# schematic.net
KiCad netlist of a schematic drawn in EasyEDA
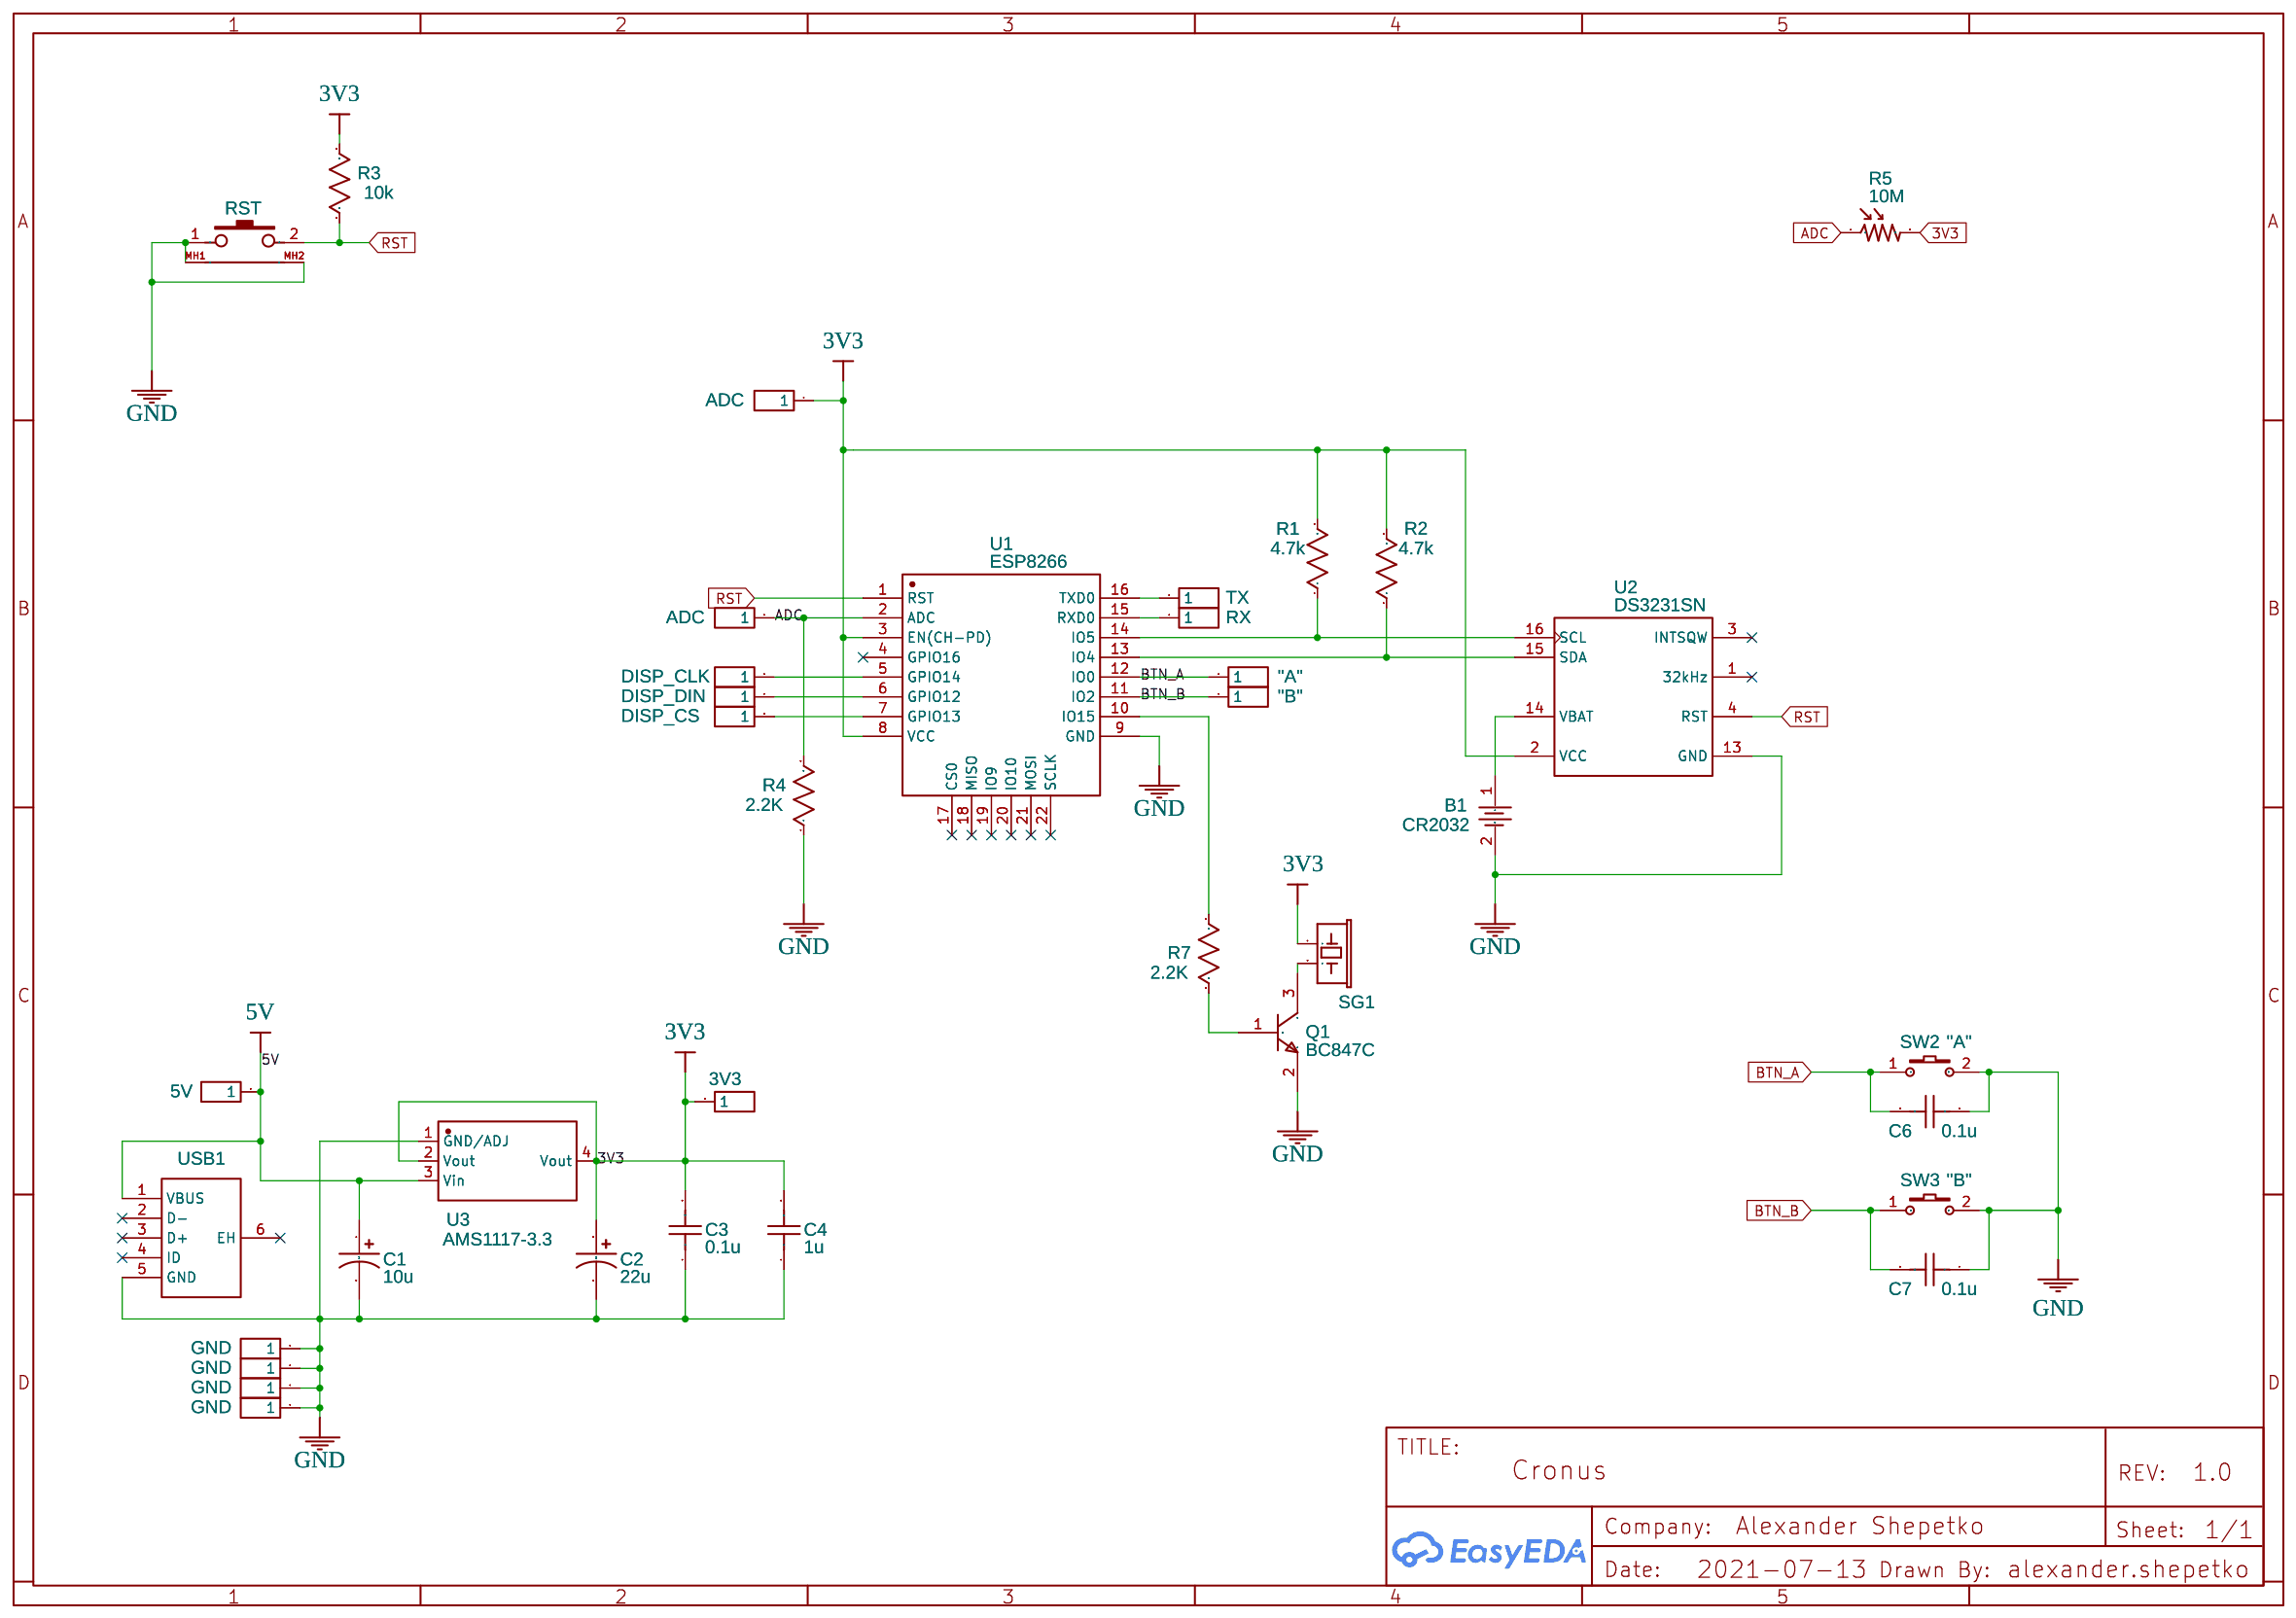
[diagram p0: schematic sheet]

(export (version "E")
  (design (tool "Eeschema 10.0.6"))
  (components
    (comp (ref "B1")
      (value "CR2032")
      (fields (field (name "BOM_Manufacturer Part") "BS-2-1") (field (name "BOM_Supplier Part") "C70376"))
      (libsource (lib "") (part "CR2032-BS-2-1"))
    )
    (comp (ref "C1") (value "10u") (libsource (lib "") (part "C_Tan_SMD_A_US")))
    (comp (ref "C2") (value "22u") (libsource (lib "") (part "C_Tan_SMD_A_US_1")))
    (comp (ref "C3") (value "0.1u") (libsource (lib "") (part "C_0603_US")))
    (comp (ref "C4") (value "1u") (libsource (lib "") (part "C_0603_US")))
    (comp (ref "C6") (value "0.1u") (libsource (lib "") (part "C_0603_US_1")))
    (comp (ref "C7") (value "0.1u") (libsource (lib "") (part "C_0603_US_1")))
    (comp (ref "J1")
      (value "DISP_CLK")
      (fields (field (name "BOM_Supplier Part") "C81276"))
      (libsource (lib "") (part "HDR-M-2.54_1x1_1"))
    )
    (comp (ref "J2")
      (value "DISP_DIN")
      (fields (field (name "BOM_Supplier Part") "C81276"))
      (libsource (lib "") (part "HDR-M-2.54_1x1_1"))
    )
    (comp (ref "J3")
      (value "DISP_CS")
      (fields (field (name "BOM_Supplier Part") "C81276"))
      (libsource (lib "") (part "HDR-M-2.54_1x1_1"))
    )
    (comp (ref "J4")
      (value "\"A\"")
      (fields (field (name "BOM_Supplier Part") "C81276"))
      (libsource (lib "") (part "HDR-M-2.54_1x1"))
    )
    (comp (ref "J5")
      (value "TX")
      (fields (field (name "BOM_Supplier Part") "C81276"))
      (libsource (lib "") (part "HDR-M-2.54_1x1"))
    )
    (comp (ref "J6")
      (value "RX")
      (fields (field (name "BOM_Supplier Part") "C81276"))
      (libsource (lib "") (part "HDR-M-2.54_1x1"))
    )
    (comp (ref "J7")
      (value "\"B\"")
      (fields (field (name "BOM_Supplier Part") "C81276"))
      (libsource (lib "") (part "HDR-M-2.54_1x1"))
    )
    (comp (ref "J8")
      (value "ADC")
      (fields (field (name "BOM_Supplier Part") "C81276"))
      (libsource (lib "") (part "HDR-M-2.54_1x1_1"))
    )
    (comp (ref "J9")
      (value "GND")
      (fields (field (name "BOM_Supplier Part") "C81276"))
      (libsource (lib "") (part "HDR-M-2.54_1x1_1"))
    )
    (comp (ref "J10")
      (value "ADC")
      (fields (field (name "BOM_Supplier Part") "C81276"))
      (libsource (lib "") (part "HDR-M-2.54_1x1_1"))
    )
    (comp (ref "J11")
      (value "GND")
      (fields (field (name "BOM_Supplier Part") "C81276"))
      (libsource (lib "") (part "HDR-M-2.54_1x1_1"))
    )
    (comp (ref "J12")
      (value "5V")
      (fields (field (name "BOM_Supplier Part") "C81276"))
      (libsource (lib "") (part "HDR-M-2.54_1x1_1"))
    )
    (comp (ref "J13")
      (value "GND")
      (fields (field (name "BOM_Supplier Part") "C81276"))
      (libsource (lib "") (part "HDR-M-2.54_1x1_1"))
    )
    (comp (ref "J14")
      (value "GND")
      (fields (field (name "BOM_Supplier Part") "C81276"))
      (libsource (lib "") (part "HDR-M-2.54_1x1_1"))
    )
    (comp (ref "J15")
      (value "3V3")
      (fields (field (name "BOM_Supplier Part") "C81276"))
      (libsource (lib "") (part "HDR-M-2.54_1x1"))
    )
    (comp (ref "Q1") (value "BC847C") (libsource (lib "") (part "BC847CLT3")))
    (comp (ref "R1") (value "4.7k") (libsource (lib "") (part "R_0603_US")))
    (comp (ref "R2") (value "4.7k") (libsource (lib "") (part "R_0603_US")))
    (comp (ref "R3") (value "10k") (libsource (lib "") (part "R_0603_US")))
    (comp (ref "R4") (value "2.2K") (libsource (lib "") (part "R_0603_US")))
    (comp (ref "R5") (value "10M") (libsource (lib "") (part "PHOTORESPDV-P9")))
    (comp (ref "R7") (value "2.2K") (libsource (lib "") (part "R_0603_US_1")))
    (comp (ref "SG1") (value "BUZZER") (libsource (lib "") (part "BUZZER")))
    (comp (ref "SW1")
      (value "RST")
      (fields
        (field (name "BOM_Manufacturer Part") "Switch,6*6*9Plastic head,260G, 0.25mm,Side bracket")
        (field (name "BOM_Supplier Part") "C71842")
      )
      (libsource (lib "") (part "Button-6x6x9-Right-Angle"))
    )
    (comp (ref "SW2")
      (value "\"A\"")
      (fields
        (field (name "BOM_Manufacturer Part") "K2-1107ST-A4SW-06")
        (field (name "BOM_Supplier Part") "C118141")
      )
      (libsource (lib "") (part "K2-3.6×6.1_SMD"))
    )
    (comp (ref "SW3")
      (value "\"B\"")
      (fields
        (field (name "BOM_Manufacturer Part") "K2-1107ST-A4SW-06")
        (field (name "BOM_Supplier Part") "C118141")
      )
      (libsource (lib "") (part "K2-3.6×6.1_SMD"))
    )
    (comp (ref "U1")
      (value "ESP8266")
      (fields
        (field (name "BOM_Manufacturer Part") "ESP-12F(ESP8266MOD)")
        (field (name "BOM_Supplier Part") "C82891")
      )
      (libsource (lib "") (part "ESP-12F(ESP8266MOD)"))
    )
    (comp (ref "U2")
      (value "DS3231SN")
      (fields (field (name "BOM_Supplier Part") "C9866"))
      (libsource (lib "") (part "DS3231SN#"))
    )
    (comp (ref "U3")
      (value "AMS1117-3.3")
      (fields (field (name "BOM_Supplier Part") "C6186"))
      (libsource (lib "") (part "AMS1117-3.3"))
    )
    (comp (ref "USB1")
      (value "A4A0505-C-30-R")
      (fields (field (name "BOM_Supplier Part") "C694908"))
      (libsource (lib "") (part "A4A0505-C-30-R"))
    )
  )
  (nets
    (net (code "1") (name "3V3") (class "Default")
      (node (ref "C2") (pin "2") (pinfunction "1_2") (pintype "unspecified"))
      (node (ref "C3") (pin "2") (pinfunction "2_2") (pintype "unspecified"))
      (node (ref "C4") (pin "2") (pinfunction "2_2") (pintype "unspecified"))
      (node (ref "J10") (pin "1") (pinfunction "1_1") (pintype "input"))
      (node (ref "J15") (pin "1") (pinfunction "1_1") (pintype "input"))
      (node (ref "R1") (pin "2") (pinfunction "2_2") (pintype "unspecified"))
      (node (ref "R2") (pin "2") (pinfunction "2_2") (pintype "unspecified"))
      (node (ref "R3") (pin "2") (pinfunction "2_2") (pintype "unspecified"))
      (node (ref "R5") (pin "2") (pinfunction "2_2") (pintype "unspecified"))
      (node (ref "SG1") (pin "1") (pinfunction "1_1") (pintype "unspecified"))
      (node (ref "U1") (pin "3") (pinfunction "EN(CH-PD)_3") (pintype "unspecified"))
      (node (ref "U1") (pin "8") (pinfunction "VCC_8") (pintype "unspecified"))
      (node (ref "U2") (pin "2") (pinfunction "VCC_2") (pintype "passive"))
      (node (ref "U3") (pin "2") (pinfunction "Vout_2") (pintype "unspecified"))
      (node (ref "U3") (pin "4") (pinfunction "Vout_4") (pintype "unspecified"))
    )
    (net (code "2") (name "5V") (class "Default")
      (node (ref "C1") (pin "1") (pinfunction "1_1") (pintype "unspecified"))
      (node (ref "J12") (pin "1") (pinfunction "1_1") (pintype "input"))
      (node (ref "U3") (pin "3") (pinfunction "Vin_3") (pintype "unspecified"))
      (node (ref "USB1") (pin "1") (pinfunction "VBUS_1") (pintype "unspecified"))
    )
    (net (code "3") (name "ADC") (class "Default")
      (node (ref "J8") (pin "1") (pinfunction "1_1") (pintype "input"))
      (node (ref "R4") (pin "2") (pinfunction "2_2") (pintype "unspecified"))
      (node (ref "R5") (pin "1") (pinfunction "1_1") (pintype "unspecified"))
      (node (ref "U1") (pin "2") (pinfunction "ADC_2") (pintype "unspecified"))
    )
    (net (code "4") (name "BTN_A") (class "Default")
      (node (ref "C6") (pin "2") (pinfunction "2_2") (pintype "unspecified"))
      (node (ref "J4") (pin "1") (pinfunction "1_1") (pintype "input"))
      (node (ref "SW2") (pin "1") (pinfunction "1_1") (pintype "unspecified"))
      (node (ref "U1") (pin "12") (pinfunction "IO0_12") (pintype "unspecified"))
    )
    (net (code "5") (name "BTN_B") (class "Default")
      (node (ref "C7") (pin "2") (pinfunction "2_2") (pintype "unspecified"))
      (node (ref "J7") (pin "1") (pinfunction "1_1") (pintype "input"))
      (node (ref "SW3") (pin "1") (pinfunction "1_1") (pintype "unspecified"))
      (node (ref "U1") (pin "11") (pinfunction "IO2_11") (pintype "unspecified"))
    )
    (net (code "6") (name "GND") (class "Default")
      (node (ref "B1") (pin "2") (pinfunction "2_2") (pintype "input"))
      (node (ref "C1") (pin "2") (pinfunction "2_2") (pintype "unspecified"))
      (node (ref "C2") (pin "1") (pinfunction "2_1") (pintype "unspecified"))
      (node (ref "C3") (pin "1") (pinfunction "1_1") (pintype "unspecified"))
      (node (ref "C4") (pin "1") (pinfunction "1_1") (pintype "unspecified"))
      (node (ref "C6") (pin "1") (pinfunction "1_1") (pintype "unspecified"))
      (node (ref "C7") (pin "1") (pinfunction "1_1") (pintype "unspecified"))
      (node (ref "J11") (pin "1") (pinfunction "1_1") (pintype "input"))
      (node (ref "J13") (pin "1") (pinfunction "1_1") (pintype "input"))
      (node (ref "J14") (pin "1") (pinfunction "1_1") (pintype "input"))
      (node (ref "J9") (pin "1") (pinfunction "1_1") (pintype "input"))
      (node (ref "Q1") (pin "2") (pinfunction "E_2") (pintype "unspecified"))
      (node (ref "R4") (pin "1") (pinfunction "1_1") (pintype "unspecified"))
      (node (ref "SW1") (pin "1") (pinfunction "1_1") (pintype "input"))
      (node (ref "SW1") (pin "MH1") (pinfunction "MH1_MH1") (pintype "input"))
      (node (ref "SW1") (pin "MH2") (pinfunction "MH2_MH2") (pintype "input"))
      (node (ref "SW2") (pin "2") (pinfunction "2_2") (pintype "unspecified"))
      (node (ref "SW3") (pin "2") (pinfunction "2_2") (pintype "unspecified"))
      (node (ref "U1") (pin "9") (pinfunction "GND_9") (pintype "unspecified"))
      (node (ref "U2") (pin "13") (pinfunction "GND_13") (pintype "passive"))
      (node (ref "U3") (pin "1") (pinfunction "GND/ADJ_1") (pintype "unspecified"))
      (node (ref "USB1") (pin "5") (pinfunction "GND_5") (pintype "unspecified"))
    )
    (net (code "7") (name "Net-(Q1-B)") (class "Default")
      (node (ref "Q1") (pin "1") (pinfunction "B_1") (pintype "unspecified"))
      (node (ref "R7") (pin "2") (pinfunction "2_2") (pintype "unspecified"))
    )
    (net (code "8") (name "Net-(Q1-C)") (class "Default")
      (node (ref "Q1") (pin "3") (pinfunction "C_3") (pintype "unspecified"))
      (node (ref "SG1") (pin "2") (pinfunction "1_2") (pintype "unspecified"))
    )
    (net (code "9") (name "Net-(U1-GPIO12)") (class "Default")
      (node (ref "J2") (pin "1") (pinfunction "1_1") (pintype "input"))
      (node (ref "U1") (pin "6") (pinfunction "GPIO12_6") (pintype "unspecified"))
    )
    (net (code "10") (name "Net-(U1-GPIO13)") (class "Default")
      (node (ref "J3") (pin "1") (pinfunction "1_1") (pintype "input"))
      (node (ref "U1") (pin "7") (pinfunction "GPIO13_7") (pintype "unspecified"))
    )
    (net (code "11") (name "Net-(U1-GPIO14)") (class "Default")
      (node (ref "J1") (pin "1") (pinfunction "1_1") (pintype "input"))
      (node (ref "U1") (pin "5") (pinfunction "GPIO14_5") (pintype "unspecified"))
    )
    (net (code "12") (name "Net-(U1-IO4)") (class "Default")
      (node (ref "R2") (pin "1") (pinfunction "1_1") (pintype "unspecified"))
      (node (ref "U1") (pin "13") (pinfunction "IO4_13") (pintype "unspecified"))
      (node (ref "U2") (pin "15") (pinfunction "SDA_15") (pintype "bidirectional"))
    )
    (net (code "13") (name "Net-(U1-IO5)") (class "Default")
      (node (ref "R1") (pin "1") (pinfunction "1_1") (pintype "unspecified"))
      (node (ref "U1") (pin "14") (pinfunction "IO5_14") (pintype "unspecified"))
      (node (ref "U2") (pin "16") (pinfunction "SCL_16") (pintype "unspecified"))
    )
    (net (code "14") (name "Net-(U1-IO15)") (class "Default")
      (node (ref "R7") (pin "1") (pinfunction "1_1") (pintype "unspecified"))
      (node (ref "U1") (pin "10") (pinfunction "IO15_10") (pintype "unspecified"))
    )
    (net (code "15") (name "Net-(U1-RXD0)") (class "Default")
      (node (ref "J6") (pin "1") (pinfunction "1_1") (pintype "input"))
      (node (ref "U1") (pin "15") (pinfunction "RXD0_15") (pintype "unspecified"))
    )
    (net (code "16") (name "Net-(U1-TXD0)") (class "Default")
      (node (ref "J5") (pin "1") (pinfunction "1_1") (pintype "input"))
      (node (ref "U1") (pin "16") (pinfunction "TXD0_16") (pintype "unspecified"))
    )
    (net (code "17") (name "Net-(U2-VBAT)") (class "Default")
      (node (ref "B1") (pin "1") (pinfunction "1_1") (pintype "input"))
      (node (ref "U2") (pin "14") (pinfunction "VBAT_14") (pintype "passive"))
    )
    (net (code "18") (name "RST") (class "Default")
      (node (ref "R3") (pin "1") (pinfunction "1_1") (pintype "unspecified"))
      (node (ref "SW1") (pin "2") (pinfunction "2_2") (pintype "input"))
      (node (ref "U1") (pin "1") (pinfunction "RST_1") (pintype "unspecified"))
      (node (ref "U2") (pin "4") (pinfunction "RST_4") (pintype "bidirectional"))
    )
    (net (code "19") (name "unconnected-(U1-CS0-Pad17)") (class "Default")
      (node (ref "U1") (pin "17") (pinfunction "CS0_17") (pintype "unspecified+no_connect"))
    )
    (net (code "20") (name "unconnected-(U1-GPIO16-Pad4)") (class "Default")
      (node (ref "U1") (pin "4") (pinfunction "GPIO16_4") (pintype "unspecified+no_connect"))
    )
    (net (code "21") (name "unconnected-(U1-IO9-Pad19)") (class "Default")
      (node (ref "U1") (pin "19") (pinfunction "IO9_19") (pintype "unspecified+no_connect"))
    )
    (net (code "22") (name "unconnected-(U1-IO10-Pad20)") (class "Default")
      (node (ref "U1") (pin "20") (pinfunction "IO10_20") (pintype "unspecified+no_connect"))
    )
    (net (code "23") (name "unconnected-(U1-MISO-Pad18)") (class "Default")
      (node (ref "U1") (pin "18") (pinfunction "MISO_18") (pintype "unspecified+no_connect"))
    )
    (net (code "24") (name "unconnected-(U1-MOSI-Pad21)") (class "Default")
      (node (ref "U1") (pin "21") (pinfunction "MOSI_21") (pintype "unspecified+no_connect"))
    )
    (net (code "25") (name "unconnected-(U1-SCLK-Pad22)") (class "Default")
      (node (ref "U1") (pin "22") (pinfunction "SCLK_22") (pintype "unspecified+no_connect"))
    )
    (net (code "26") (name "unconnected-(U2-32kHz-Pad1)") (class "Default")
      (node (ref "U2") (pin "1") (pinfunction "32kHz_1") (pintype "unspecified+no_connect"))
    )
    (net (code "27") (name "unconnected-(U2-INTSQW-Pad3)") (class "Default")
      (node (ref "U2") (pin "3") (pinfunction "INTSQW_3") (pintype "unspecified+no_connect"))
    )
    (net (code "28") (name "unconnected-(USB1-D+-Pad3)") (class "Default")
      (node (ref "USB1") (pin "3") (pinfunction "D+_3") (pintype "unspecified+no_connect"))
    )
    (net (code "29") (name "unconnected-(USB1-D--Pad2)") (class "Default")
      (node (ref "USB1") (pin "2") (pinfunction "D-_2") (pintype "unspecified+no_connect"))
    )
    (net (code "30") (name "unconnected-(USB1-EH-Pad6)") (class "Default")
      (node (ref "USB1") (pin "6") (pinfunction "EH_6") (pintype "unspecified+no_connect"))
    )
    (net (code "31") (name "unconnected-(USB1-ID-Pad4)") (class "Default")
      (node (ref "USB1") (pin "4") (pinfunction "ID_4") (pintype "unspecified+no_connect"))
    )
  )
)
